# Converter_Unit.net
KiCad netlist of a schematic drawn in Altium Designer
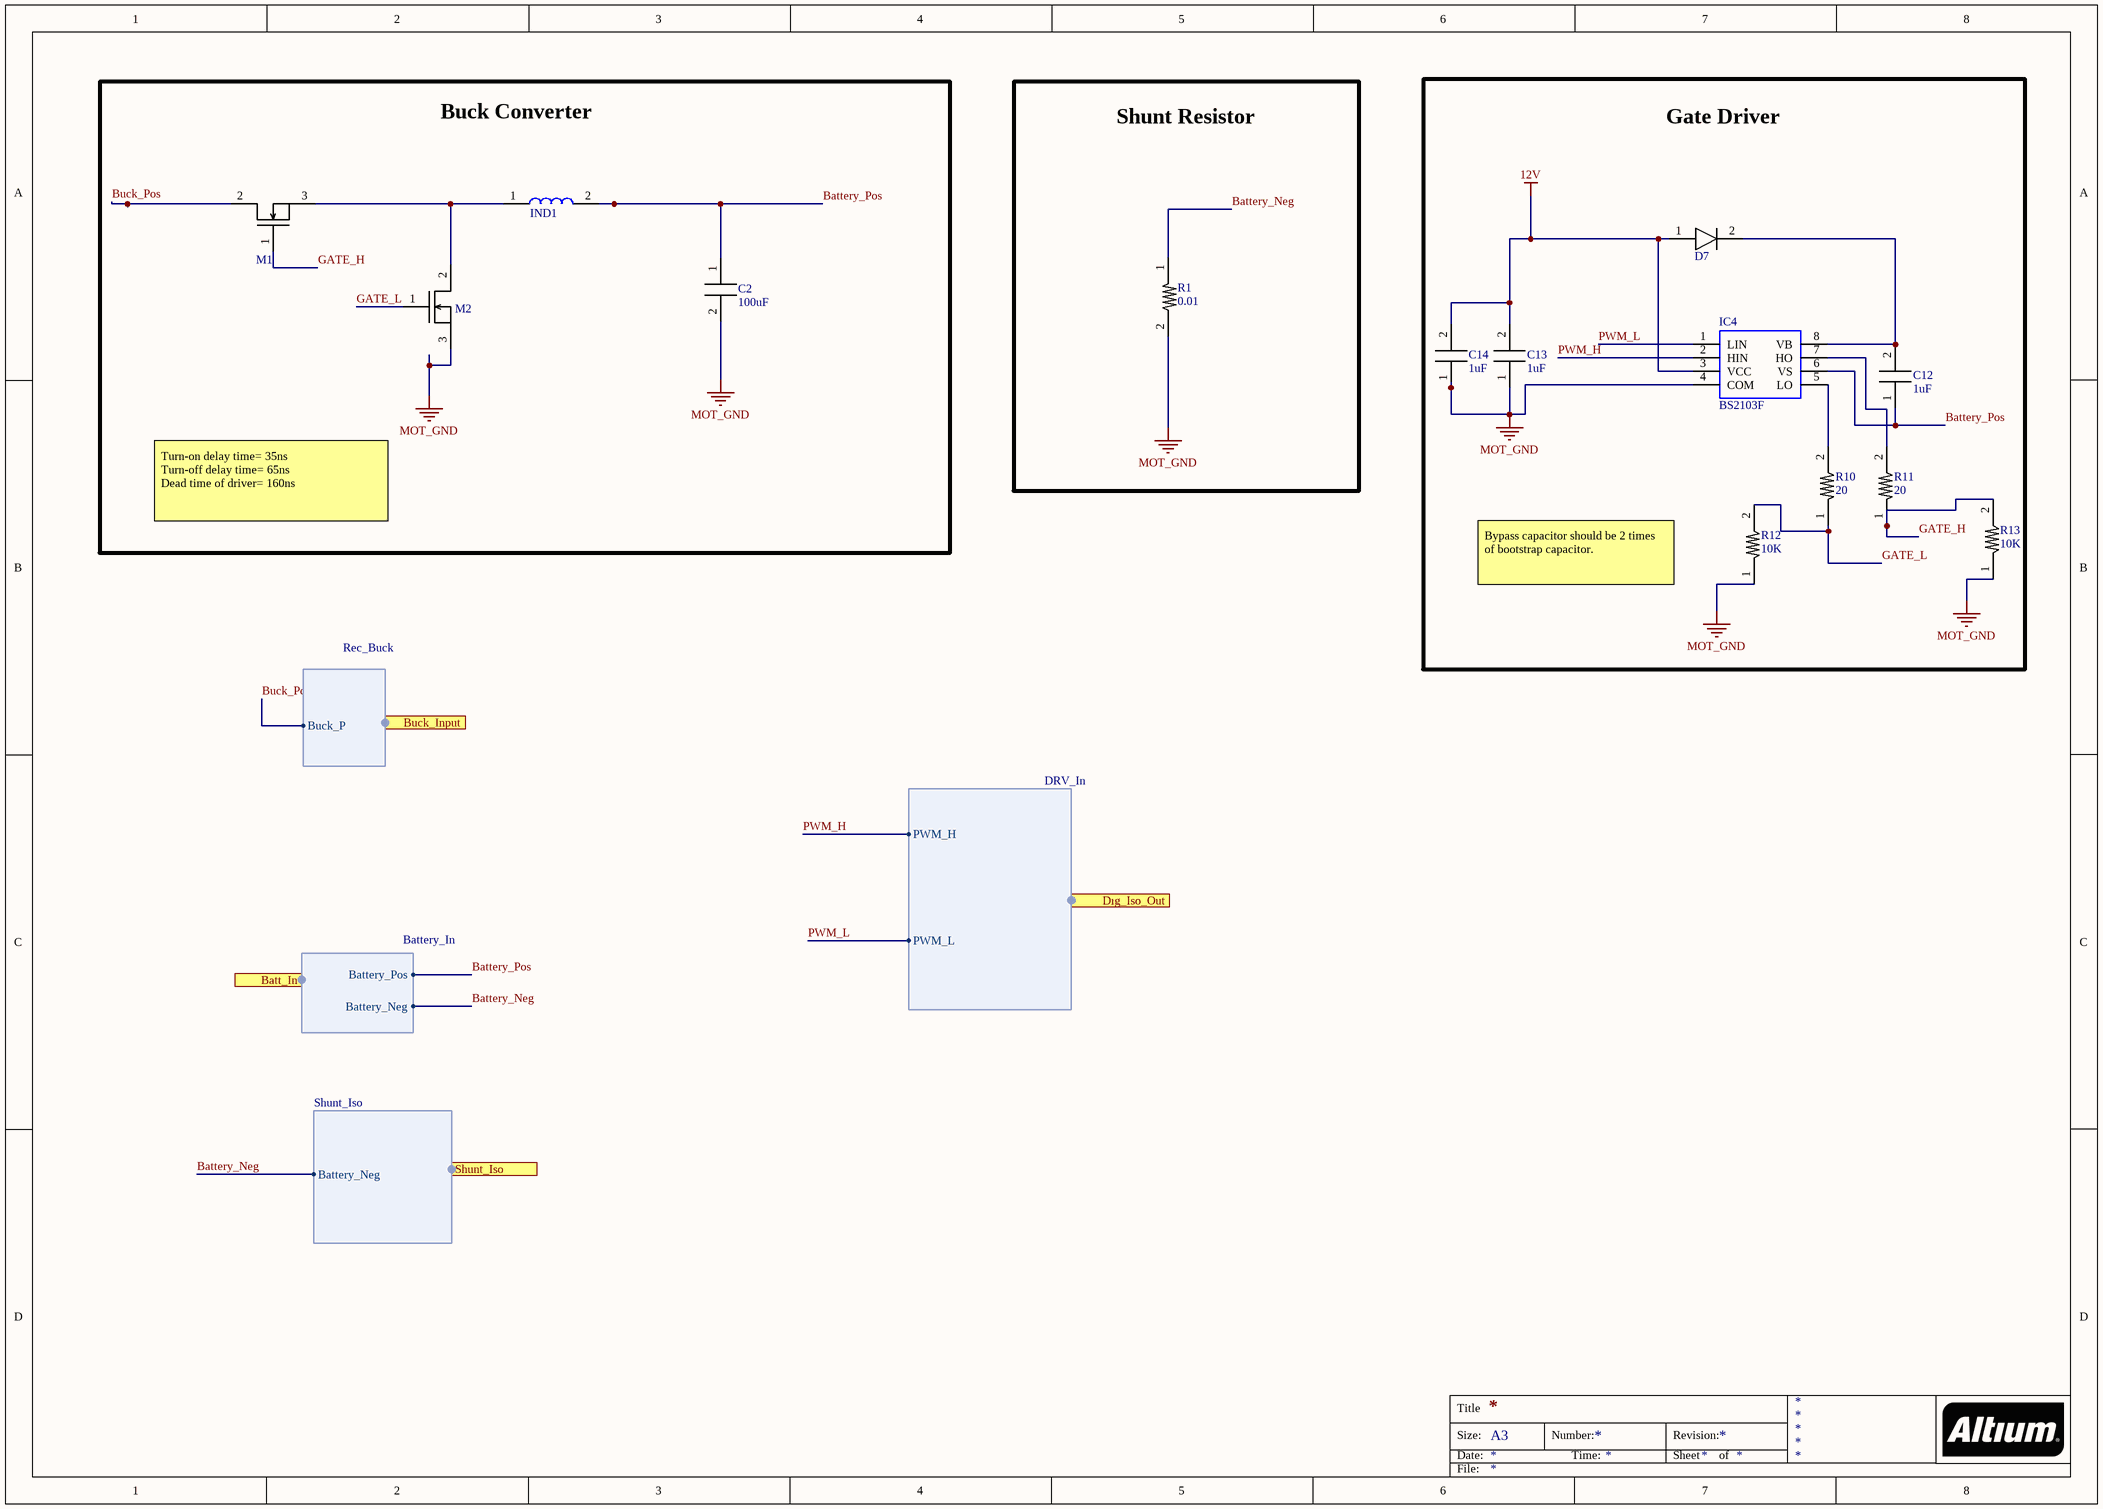
[diagram p0: Converter_Unit.SchDoc]

(export (version "E")
  (design (tool "Eeschema 10.0.6"))
  (components
    (comp (ref "C2")
      (value "CAP 100uF 860020573008")
      (footprint "860020573008")
      (fields (field (name "PARAMETER 1") "100uF"))
      (libsource (lib "Schlib1") (part "CAP 100uF 860020573008"))
    )
    (comp (ref "C12")
      (value "CAP 1uF")
      (footprint "0603_CAP")
      (fields (field (name "PARAMETER 1") "1uF"))
      (libsource (lib "Schlib1") (part "CAP 1uF"))
    )
    (comp (ref "C13")
      (value "CAP 1uF")
      (footprint "0603_CAP")
      (fields (field (name "PARAMETER 1") "1uF"))
      (libsource (lib "Schlib1") (part "CAP 1uF"))
    )
    (comp (ref "C14")
      (value "CAP 1uF")
      (footprint "0603_CAP")
      (fields (field (name "PARAMETER 1") "1uF"))
      (libsource (lib "Schlib1") (part "CAP 1uF"))
    )
    (comp (ref "D7")
      (value "DI S2GTR")
      (footprint "S2GTR")
      (description "DI, S2GTR, 400V, 2A")
      (libsource (lib "Schlib1") (part "DI S2GTR"))
    )
    (comp (ref "IC4")
      (value "BS2103F")
      (footprint "BS2103F")
      (libsource (lib "Schlib1") (part "IC DRV, HALF-B, BS2103F"))
    )
    (comp (ref "IND1")
      (value "IND, 1mH, B82615B2202M001")
      (footprint "AIRD")
      (description "IND, 5mH, B82615B2202M001, 250V, 2A")
      (libsource (lib "Schlib1") (part "IND, 1mH, B82615B2202M001"))
    )
    (comp (ref "M1")
      (value "M?")
      (footprint "FDD5N50NZ")
      (description "MOS, N-CH, FDD5N550NZ, 2A")
      (libsource (lib "Schlib1") (part "MOS, N-CH, FDD5N550NZ"))
    )
    (comp (ref "M2")
      (value "M?")
      (footprint "FDD5N50NZ")
      (description "MOS, N-CH, FDD5N550NZ, 2A")
      (libsource (lib "Schlib1") (part "MOS, N-CH, FDD5N550NZ"))
    )
    (comp (ref "R1")
      (value "RES, 0.01, 0402, Shunt")
      (footprint "RES_0402")
      (description "RES, 0.01, 0402, Shunt, CSS0402FT10L0")
      (fields (field (name "PARAMETER 1") "0.01"))
      (libsource (lib "Schlib1") (part "RES, 0.01, 0402, Shunt"))
    )
    (comp (ref "R10")
      (value "RES, 20, 0603")
      (footprint "0603_RES")
      (fields (field (name "PARAMETER 1") "20"))
      (libsource (lib "Schlib1") (part "RES, 20, 0603"))
    )
    (comp (ref "R11")
      (value "RES, 20, 0603")
      (footprint "0603_RES")
      (fields (field (name "PARAMETER 1") "20"))
      (libsource (lib "Schlib1") (part "RES, 20, 0603"))
    )
    (comp (ref "R12")
      (value "RES, 10K, 0603")
      (footprint "0603_RES")
      (fields (field (name "PARAMETER 1") "10K"))
      (libsource (lib "Schlib1") (part "RES, 10K, 0603"))
    )
    (comp (ref "R13")
      (value "RES, 10K, 0603")
      (footprint "0603_RES")
      (fields (field (name "PARAMETER 1") "10K"))
      (libsource (lib "Schlib1") (part "RES, 10K, 0603"))
    )
  )
  (nets
    (net (code "5") (name "/Battery_Neg") (class "Default")
      (node (ref "R1") (pin "1") (pinfunction "1_1") (pintype "passive"))
    )
    (net (code "6") (name "/Battery_Pos") (class "Default")
      (node (ref "C12") (pin "1") (pinfunction "1_1") (pintype "passive"))
      (node (ref "C2") (pin "1") (pinfunction "1_1") (pintype "passive"))
      (node (ref "IC4") (pin "6") (pinfunction "VS_6") (pintype "passive"))
      (node (ref "IND1") (pin "2") (pinfunction "2_2") (pintype "passive"))
    )
    (net (code "7") (name "/Buck_Pos") (class "Default")
      (node (ref "M1") (pin "2") (pinfunction "2_2") (pintype "passive"))
    )
    (net (code "8") (name "/GATE_H") (class "Default")
      (node (ref "M1") (pin "1") (pinfunction "1_1") (pintype "passive"))
      (node (ref "R11") (pin "1") (pinfunction "1_1") (pintype "passive"))
      (node (ref "R13") (pin "2") (pinfunction "2_2") (pintype "passive"))
    )
    (net (code "9") (name "/GATE_L") (class "Default")
      (node (ref "M2") (pin "1") (pinfunction "1_1") (pintype "passive"))
      (node (ref "R10") (pin "1") (pinfunction "1_1") (pintype "passive"))
      (node (ref "R12") (pin "2") (pinfunction "2_2") (pintype "passive"))
    )
    (net (code "10") (name "/PWM_H") (class "Default")
      (node (ref "IC4") (pin "2") (pinfunction "HIN_2") (pintype "passive"))
    )
    (net (code "11") (name "/PWM_L") (class "Default")
      (node (ref "IC4") (pin "1") (pinfunction "LIN_1") (pintype "passive"))
    )
    (net (code "16") (name "12V") (class "Default")
      (node (ref "C13") (pin "2") (pinfunction "2_2") (pintype "passive"))
      (node (ref "C14") (pin "2") (pinfunction "2_2") (pintype "passive"))
      (node (ref "D7") (pin "1") (pinfunction "Anode_1") (pintype "passive"))
      (node (ref "IC4") (pin "3") (pinfunction "VCC_3") (pintype "passive"))
    )
    (net (code "17") (name "MOT_GND") (class "Default")
      (node (ref "C13") (pin "1") (pinfunction "1_1") (pintype "passive"))
      (node (ref "C14") (pin "1") (pinfunction "1_1") (pintype "passive"))
      (node (ref "C2") (pin "2") (pinfunction "2_2") (pintype "passive"))
      (node (ref "IC4") (pin "4") (pinfunction "COM_4") (pintype "passive"))
      (node (ref "M2") (pin "3") (pinfunction "3_3") (pintype "passive"))
      (node (ref "R1") (pin "2") (pinfunction "2_2") (pintype "passive"))
      (node (ref "R12") (pin "1") (pinfunction "1_1") (pintype "passive"))
      (node (ref "R13") (pin "1") (pinfunction "1_1") (pintype "passive"))
    )
    (net (code "18") (name "Net-(D7-Cathode)") (class "Default")
      (node (ref "C12") (pin "2") (pinfunction "2_2") (pintype "passive"))
      (node (ref "D7") (pin "2") (pinfunction "Cathode_2") (pintype "passive"))
      (node (ref "IC4") (pin "8") (pinfunction "VB_8") (pintype "passive"))
    )
    (net (code "19") (name "Net-(IC4-HO)") (class "Default")
      (node (ref "IC4") (pin "7") (pinfunction "HO_7") (pintype "passive"))
      (node (ref "R11") (pin "2") (pinfunction "2_2") (pintype "passive"))
    )
    (net (code "20") (name "Net-(IC4-LO)") (class "Default")
      (node (ref "IC4") (pin "5") (pinfunction "LO_5") (pintype "passive"))
      (node (ref "R10") (pin "2") (pinfunction "2_2") (pintype "passive"))
    )
    (net (code "21") (name "Net-(IND1-Pad1)") (class "Default")
      (node (ref "IND1") (pin "1") (pinfunction "1_1") (pintype "passive"))
      (node (ref "M1") (pin "3") (pinfunction "3_3") (pintype "passive"))
      (node (ref "M2") (pin "2") (pinfunction "2_2") (pintype "passive"))
    )
  )
)
